# Dumptruck2017.net
KiCad netlist of a schematic drawn in EAGLE
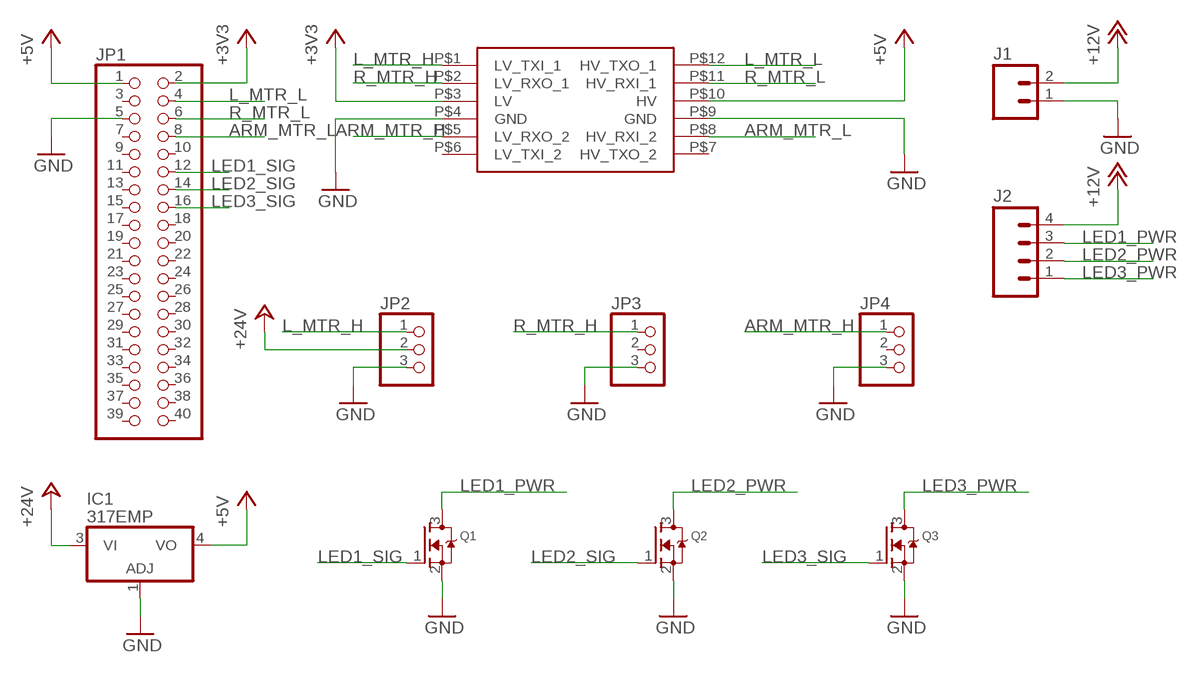
[diagram p0: schematic, sheet 1]

(export (version "E")
  (design (tool "Eeschema 10.0.6"))
  (components
    (comp (ref "IC1")
      (value "317EMP")
      (footprint "eagle-import:SOT223")
      (libsource (lib "eagle-import") (part "317EMP"))
    )
    (comp (ref "J1")
      (value "M02LOCK")
      (footprint "eagle-import:1X02_LOCK")
      (libsource (lib "eagle-import") (part "M02LOCK"))
    )
    (comp (ref "J2")
      (value "M04LOCK")
      (footprint "eagle-import:1X04_LOCK")
      (libsource (lib "eagle-import") (part "M04LOCK"))
    )
    (comp (ref "JP1")
      (value "PINHD-2X20")
      (footprint "eagle-import:2X20")
      (libsource (lib "eagle-import") (part "PINHD-2X20"))
    )
    (comp (ref "JP2")
      (value "PINHD-1X3")
      (footprint "eagle-import:1X03")
      (libsource (lib "eagle-import") (part "PINHD-1X3"))
    )
    (comp (ref "JP3")
      (value "PINHD-1X3")
      (footprint "eagle-import:1X03")
      (libsource (lib "eagle-import") (part "PINHD-1X3"))
    )
    (comp (ref "JP4")
      (value "PINHD-1X3")
      (footprint "eagle-import:1X03")
      (libsource (lib "eagle-import") (part "PINHD-1X3"))
    )
    (comp (ref "Q1")
      (value "MOSFET-NREFLOW")
      (footprint "eagle-import:SOT23")
      (libsource (lib "eagle-import") (part "MOSFET-NREFLOW"))
    )
    (comp (ref "Q2")
      (value "MOSFET-NREFLOW")
      (footprint "eagle-import:SOT23")
      (libsource (lib "eagle-import") (part "MOSFET-NREFLOW"))
    )
    (comp (ref "Q3")
      (value "MOSFET-NREFLOW")
      (footprint "eagle-import:SOT23")
      (libsource (lib "eagle-import") (part "MOSFET-NREFLOW"))
    )
    (comp (ref "U$1")
      (value "LOGIC_LEVEL_CONVERTER")
      (footprint "eagle-import:LOGIC_LEVEL_CONVERTER")
      (libsource (lib "eagle-import") (part "LOGIC_LEVEL_CONVERTER"))
    )
  )
  (nets
    (net (code "1") (name "+3V3") (class "Default")
      (node (ref "JP1") (pin "2") (pinfunction "2_2") (pintype "passive"))
      (node (ref "U$1") (pin "P$3") (pinfunction "LV_P$3") (pintype "bidirectional"))
    )
    (net (code "2") (name "+5V") (class "Default")
      (node (ref "IC1") (pin "4") (pinfunction "VO_4") (pintype "passive"))
      (node (ref "JP1") (pin "1") (pinfunction "1_1") (pintype "passive"))
      (node (ref "U$1") (pin "P$10") (pinfunction "HV_P$10") (pintype "bidirectional"))
    )
    (net (code "3") (name "+12V") (class "Default")
      (node (ref "J1") (pin "2") (pinfunction "2_2") (pintype "passive"))
      (node (ref "J2") (pin "4") (pinfunction "4_4") (pintype "passive"))
    )
    (net (code "4") (name "+24V") (class "Default")
      (node (ref "IC1") (pin "3") (pinfunction "VI_3") (pintype "input"))
      (node (ref "JP2") (pin "2") (pinfunction "2_2") (pintype "passive"))
    )
    (net (code "5") (name "/ARM_MTR_H") (class "Default")
      (node (ref "JP4") (pin "1") (pinfunction "1_1") (pintype "passive"))
      (node (ref "U$1") (pin "P$5") (pinfunction "LV_RXO_2_P$5") (pintype "bidirectional"))
    )
    (net (code "6") (name "/ARM_MTR_L") (class "Default")
      (node (ref "JP1") (pin "8") (pinfunction "8_8") (pintype "passive"))
      (node (ref "U$1") (pin "P$8") (pinfunction "HV_RXI_2_P$8") (pintype "bidirectional"))
    )
    (net (code "7") (name "/LED1_PWR") (class "Default")
      (node (ref "J2") (pin "3") (pinfunction "3_3") (pintype "passive"))
      (node (ref "Q1") (pin "3") (pinfunction "D_3") (pintype "bidirectional"))
    )
    (net (code "8") (name "/LED1_SIG") (class "Default")
      (node (ref "JP1") (pin "12") (pinfunction "12_12") (pintype "passive"))
      (node (ref "Q1") (pin "1") (pinfunction "G_1") (pintype "bidirectional"))
    )
    (net (code "9") (name "/LED2_PWR") (class "Default")
      (node (ref "J2") (pin "2") (pinfunction "2_2") (pintype "passive"))
      (node (ref "Q2") (pin "3") (pinfunction "D_3") (pintype "bidirectional"))
    )
    (net (code "10") (name "/LED2_SIG") (class "Default")
      (node (ref "JP1") (pin "14") (pinfunction "14_14") (pintype "passive"))
      (node (ref "Q2") (pin "1") (pinfunction "G_1") (pintype "bidirectional"))
    )
    (net (code "11") (name "/LED3_PWR") (class "Default")
      (node (ref "J2") (pin "1") (pinfunction "1_1") (pintype "passive"))
      (node (ref "Q3") (pin "3") (pinfunction "D_3") (pintype "bidirectional"))
    )
    (net (code "12") (name "/LED3_SIG") (class "Default")
      (node (ref "JP1") (pin "16") (pinfunction "16_16") (pintype "passive"))
      (node (ref "Q3") (pin "1") (pinfunction "G_1") (pintype "bidirectional"))
    )
    (net (code "13") (name "/L_MTR_H") (class "Default")
      (node (ref "JP2") (pin "1") (pinfunction "1_1") (pintype "passive"))
      (node (ref "U$1") (pin "P$1") (pinfunction "LV_TXI_1_P$1") (pintype "bidirectional"))
    )
    (net (code "14") (name "/L_MTR_L") (class "Default")
      (node (ref "JP1") (pin "4") (pinfunction "4_4") (pintype "passive"))
      (node (ref "U$1") (pin "P$12") (pinfunction "HV_TXO_1_P$12") (pintype "bidirectional"))
    )
    (net (code "15") (name "/R_MTR_H") (class "Default")
      (node (ref "JP3") (pin "1") (pinfunction "1_1") (pintype "passive"))
      (node (ref "U$1") (pin "P$2") (pinfunction "LV_RXO_1_P$2") (pintype "bidirectional"))
    )
    (net (code "16") (name "/R_MTR_L") (class "Default")
      (node (ref "JP1") (pin "6") (pinfunction "6_6") (pintype "passive"))
      (node (ref "U$1") (pin "P$11") (pinfunction "HV_RXI_1_P$11") (pintype "bidirectional"))
    )
    (net (code "17") (name "GND") (class "Default")
      (node (ref "IC1") (pin "1") (pinfunction "ADJ_1") (pintype "input"))
      (node (ref "J1") (pin "1") (pinfunction "1_1") (pintype "passive"))
      (node (ref "JP1") (pin "5") (pinfunction "5_5") (pintype "passive"))
      (node (ref "JP2") (pin "3") (pinfunction "3_3") (pintype "passive"))
      (node (ref "JP3") (pin "3") (pinfunction "3_3") (pintype "passive"))
      (node (ref "JP4") (pin "3") (pinfunction "3_3") (pintype "passive"))
      (node (ref "Q1") (pin "2") (pinfunction "S_2") (pintype "bidirectional"))
      (node (ref "Q2") (pin "2") (pinfunction "S_2") (pintype "bidirectional"))
      (node (ref "Q3") (pin "2") (pinfunction "S_2") (pintype "bidirectional"))
      (node (ref "U$1") (pin "P$4") (pinfunction "GND_P$4") (pintype "bidirectional"))
      (node (ref "U$1") (pin "P$9") (pinfunction "GND_P$9") (pintype "bidirectional"))
    )
    (net (code "18") (name "unconnected-(JP1-Pad3)") (class "Default")
      (node (ref "JP1") (pin "3") (pinfunction "3_3") (pintype "passive"))
    )
    (net (code "19") (name "unconnected-(JP1-Pad7)") (class "Default")
      (node (ref "JP1") (pin "7") (pinfunction "7_7") (pintype "passive"))
    )
    (net (code "20") (name "unconnected-(JP1-Pad9)") (class "Default")
      (node (ref "JP1") (pin "9") (pinfunction "9_9") (pintype "passive"))
    )
    (net (code "21") (name "unconnected-(JP1-Pad10)") (class "Default")
      (node (ref "JP1") (pin "10") (pinfunction "10_10") (pintype "passive"))
    )
    (net (code "22") (name "unconnected-(JP1-Pad11)") (class "Default")
      (node (ref "JP1") (pin "11") (pinfunction "11_11") (pintype "passive"))
    )
    (net (code "23") (name "unconnected-(JP1-Pad13)") (class "Default")
      (node (ref "JP1") (pin "13") (pinfunction "13_13") (pintype "passive"))
    )
    (net (code "24") (name "unconnected-(JP1-Pad15)") (class "Default")
      (node (ref "JP1") (pin "15") (pinfunction "15_15") (pintype "passive"))
    )
    (net (code "25") (name "unconnected-(JP1-Pad17)") (class "Default")
      (node (ref "JP1") (pin "17") (pinfunction "17_17") (pintype "passive"))
    )
    (net (code "26") (name "unconnected-(JP1-Pad18)") (class "Default")
      (node (ref "JP1") (pin "18") (pinfunction "18_18") (pintype "passive"))
    )
    (net (code "27") (name "unconnected-(JP1-Pad19)") (class "Default")
      (node (ref "JP1") (pin "19") (pinfunction "19_19") (pintype "passive"))
    )
    (net (code "28") (name "unconnected-(JP1-Pad20)") (class "Default")
      (node (ref "JP1") (pin "20") (pinfunction "20_20") (pintype "passive"))
    )
    (net (code "29") (name "unconnected-(JP1-Pad21)") (class "Default")
      (node (ref "JP1") (pin "21") (pinfunction "21_21") (pintype "passive"))
    )
    (net (code "30") (name "unconnected-(JP1-Pad22)") (class "Default")
      (node (ref "JP1") (pin "22") (pinfunction "22_22") (pintype "passive"))
    )
    (net (code "31") (name "unconnected-(JP1-Pad23)") (class "Default")
      (node (ref "JP1") (pin "23") (pinfunction "23_23") (pintype "passive"))
    )
    (net (code "32") (name "unconnected-(JP1-Pad24)") (class "Default")
      (node (ref "JP1") (pin "24") (pinfunction "24_24") (pintype "passive"))
    )
    (net (code "33") (name "unconnected-(JP1-Pad25)") (class "Default")
      (node (ref "JP1") (pin "25") (pinfunction "25_25") (pintype "passive"))
    )
    (net (code "34") (name "unconnected-(JP1-Pad26)") (class "Default")
      (node (ref "JP1") (pin "26") (pinfunction "26_26") (pintype "passive"))
    )
    (net (code "35") (name "unconnected-(JP1-Pad27)") (class "Default")
      (node (ref "JP1") (pin "27") (pinfunction "27_27") (pintype "passive"))
    )
    (net (code "36") (name "unconnected-(JP1-Pad28)") (class "Default")
      (node (ref "JP1") (pin "28") (pinfunction "28_28") (pintype "passive"))
    )
    (net (code "37") (name "unconnected-(JP1-Pad29)") (class "Default")
      (node (ref "JP1") (pin "29") (pinfunction "29_29") (pintype "passive"))
    )
    (net (code "38") (name "unconnected-(JP1-Pad30)") (class "Default")
      (node (ref "JP1") (pin "30") (pinfunction "30_30") (pintype "passive"))
    )
    (net (code "39") (name "unconnected-(JP1-Pad31)") (class "Default")
      (node (ref "JP1") (pin "31") (pinfunction "31_31") (pintype "passive"))
    )
    (net (code "40") (name "unconnected-(JP1-Pad32)") (class "Default")
      (node (ref "JP1") (pin "32") (pinfunction "32_32") (pintype "passive"))
    )
    (net (code "41") (name "unconnected-(JP1-Pad33)") (class "Default")
      (node (ref "JP1") (pin "33") (pinfunction "33_33") (pintype "passive"))
    )
    (net (code "42") (name "unconnected-(JP1-Pad34)") (class "Default")
      (node (ref "JP1") (pin "34") (pinfunction "34_34") (pintype "passive"))
    )
    (net (code "43") (name "unconnected-(JP1-Pad35)") (class "Default")
      (node (ref "JP1") (pin "35") (pinfunction "35_35") (pintype "passive"))
    )
    (net (code "44") (name "unconnected-(JP1-Pad36)") (class "Default")
      (node (ref "JP1") (pin "36") (pinfunction "36_36") (pintype "passive"))
    )
    (net (code "45") (name "unconnected-(JP1-Pad37)") (class "Default")
      (node (ref "JP1") (pin "37") (pinfunction "37_37") (pintype "passive"))
    )
    (net (code "46") (name "unconnected-(JP1-Pad38)") (class "Default")
      (node (ref "JP1") (pin "38") (pinfunction "38_38") (pintype "passive"))
    )
    (net (code "47") (name "unconnected-(JP1-Pad39)") (class "Default")
      (node (ref "JP1") (pin "39") (pinfunction "39_39") (pintype "passive"))
    )
    (net (code "48") (name "unconnected-(JP1-Pad40)") (class "Default")
      (node (ref "JP1") (pin "40") (pinfunction "40_40") (pintype "passive"))
    )
    (net (code "49") (name "unconnected-(JP3-Pad2)") (class "Default")
      (node (ref "JP3") (pin "2") (pinfunction "2_2") (pintype "passive"))
    )
    (net (code "50") (name "unconnected-(JP4-Pad2)") (class "Default")
      (node (ref "JP4") (pin "2") (pinfunction "2_2") (pintype "passive"))
    )
    (net (code "51") (name "unconnected-(U$1-HV_TXO_2-PadP$7)") (class "Default")
      (node (ref "U$1") (pin "P$7") (pinfunction "HV_TXO_2_P$7") (pintype "bidirectional"))
    )
    (net (code "52") (name "unconnected-(U$1-LV_TXI_2-PadP$6)") (class "Default")
      (node (ref "U$1") (pin "P$6") (pinfunction "LV_TXI_2_P$6") (pintype "bidirectional"))
    )
  )
)
